# transmitter.net
KiCad netlist of a schematic drawn in EAGLE
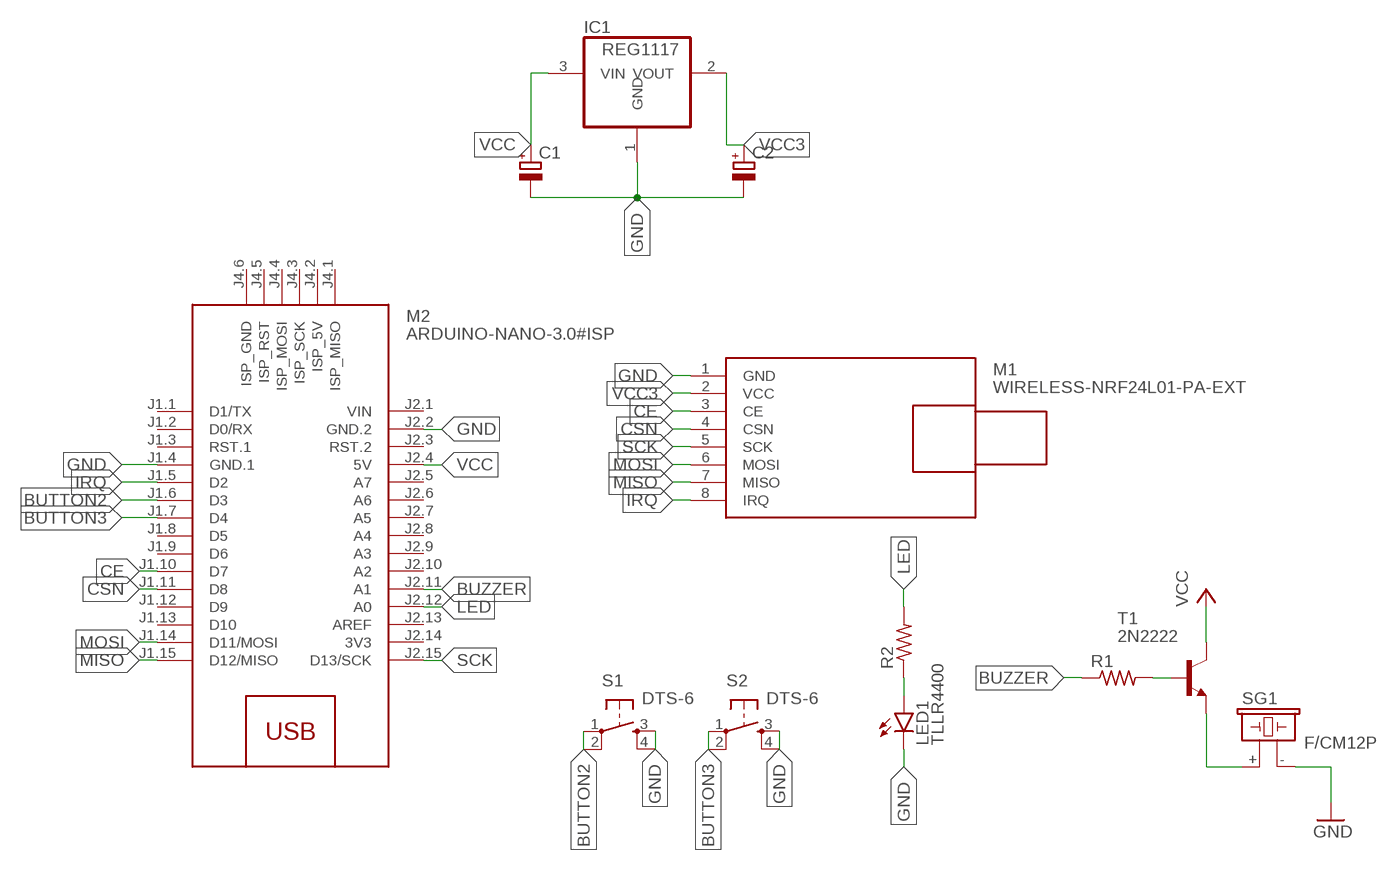
[diagram p0: schematic, sheet 1]

(export (version "E")
  (design (tool "Eeschema 10.0.6"))
  (components
    (comp (ref "C1")
      (value "CPOL-EUE2,5-6E")
      (footprint "eagle-import:E2,5-6E")
      (libsource (lib "eagle-import") (part "CPOL-EUE2,5-6E"))
    )
    (comp (ref "C2")
      (value "CPOL-EUE2,5-6E")
      (footprint "eagle-import:E2,5-6E")
      (libsource (lib "eagle-import") (part "CPOL-EUE2,5-6E"))
    )
    (comp (ref "IC1")
      (value "REG1117")
      (footprint "eagle-import:SOT223")
      (libsource (lib "eagle-import") (part "REG1117"))
    )
    (comp (ref "LED1")
      (value "TLLR4400")
      (footprint "eagle-import:LED3MM")
      (fields (field (name "MF") "VISHAY SEMICONDUCTOR"))
      (libsource (lib "eagle-import") (part "TLLR4400"))
    )
    (comp (ref "M1")
      (value "WIRELESS-NRF24L01-PA-EXT")
      (footprint "eagle-import:WIRELESS-NRF24L01-PA-EXT")
      (libsource (lib "eagle-import") (part "WIRELESS-NRF24L01-PA-EXT"))
    )
    (comp (ref "M2")
      (value "ARDUINO-NANO-3.0#ISP")
      (footprint "eagle-import:ARDUINO-NANO-3.0#ISP")
      (libsource (lib "eagle-import") (part "ARDUINO-NANO-3.0#ISP"))
    )
    (comp (ref "R1")
      (value "R-US_R0805")
      (footprint "eagle-import:R0805")
      (libsource (lib "eagle-import") (part "R-US_R0805"))
    )
    (comp (ref "R2")
      (value "R-US_R0805")
      (footprint "eagle-import:R0805")
      (libsource (lib "eagle-import") (part "R-US_R0805"))
    )
    (comp (ref "S1")
      (value "DTS-6")
      (footprint "eagle-import:DTS-6")
      (libsource (lib "eagle-import") (part "DTS-6"))
    )
    (comp (ref "S2")
      (value "DTS-6")
      (footprint "eagle-import:DTS-6")
      (libsource (lib "eagle-import") (part "DTS-6"))
    )
    (comp (ref "SG1")
      (value "F/CM12P")
      (footprint "eagle-import:F_CM12P")
      (libsource (lib "eagle-import") (part "F/CM12P"))
    )
    (comp (ref "T1")
      (value "2N2222")
      (footprint "eagle-import:TO92-EBC-OVAL")
      (libsource (lib "eagle-import") (part "2N2222"))
    )
  )
  (nets
    (net (code "1") (name "/3V3") (class "Default")
      (node (ref "M2") (pin "J2.14") (pinfunction "3V3_J2.14") (pintype "power_in"))
    )
    (net (code "2") (name "/VIN") (class "Default")
      (node (ref "M2") (pin "J2.1") (pinfunction "VIN_J2.1") (pintype "power_in"))
    )
    (net (code "3") (name "BUTTON2") (class "Default")
      (node (ref "M2") (pin "J1.6") (pinfunction "D3_J1.6") (pintype "bidirectional"))
      (node (ref "S1") (pin "1") (pinfunction "1_1") (pintype "passive"))
      (node (ref "S1") (pin "2") (pinfunction "2_2") (pintype "passive"))
    )
    (net (code "4") (name "BUTTON3") (class "Default")
      (node (ref "M2") (pin "J1.7") (pinfunction "D4_J1.7") (pintype "bidirectional"))
      (node (ref "S2") (pin "1") (pinfunction "1_1") (pintype "passive"))
      (node (ref "S2") (pin "2") (pinfunction "2_2") (pintype "passive"))
    )
    (net (code "5") (name "BUZZER") (class "Default")
      (node (ref "M2") (pin "J2.11") (pinfunction "A1_J2.11") (pintype "bidirectional"))
      (node (ref "R1") (pin "1") (pinfunction "1_1") (pintype "passive"))
    )
    (net (code "6") (name "CE") (class "Default")
      (node (ref "M1") (pin "3") (pinfunction "CE_3") (pintype "bidirectional"))
      (node (ref "M2") (pin "J1.10") (pinfunction "D7_J1.10") (pintype "bidirectional"))
    )
    (net (code "7") (name "CSN") (class "Default")
      (node (ref "M1") (pin "4") (pinfunction "CSN_4") (pintype "bidirectional"))
      (node (ref "M2") (pin "J1.11") (pinfunction "D8_J1.11") (pintype "bidirectional"))
    )
    (net (code "8") (name "GND") (class "Default")
      (node (ref "C1") (pin "-") (pinfunction "-_-") (pintype "passive"))
      (node (ref "C2") (pin "-") (pinfunction "-_-") (pintype "passive"))
      (node (ref "IC1") (pin "1") (pinfunction "GND_1") (pintype "power_in"))
      (node (ref "LED1") (pin "K") (pinfunction "C_K") (pintype "passive"))
      (node (ref "M1") (pin "1") (pinfunction "GND_1") (pintype "power_in"))
      (node (ref "M2") (pin "J1.4") (pinfunction "GND.1_J1.4") (pintype "power_in"))
      (node (ref "M2") (pin "J2.2") (pinfunction "GND.2_J2.2") (pintype "power_in"))
      (node (ref "S1") (pin "3") (pinfunction "3_3") (pintype "passive"))
      (node (ref "S1") (pin "4") (pinfunction "4_4") (pintype "passive"))
      (node (ref "S2") (pin "3") (pinfunction "3_3") (pintype "passive"))
      (node (ref "S2") (pin "4") (pinfunction "4_4") (pintype "passive"))
      (node (ref "SG1") (pin "-") (pinfunction "2_-") (pintype "passive"))
    )
    (net (code "9") (name "IRQ") (class "Default")
      (node (ref "M1") (pin "8") (pinfunction "IRQ_8") (pintype "bidirectional"))
      (node (ref "M2") (pin "J1.5") (pinfunction "D2_J1.5") (pintype "bidirectional"))
    )
    (net (code "10") (name "LED") (class "Default")
      (node (ref "M2") (pin "J2.12") (pinfunction "A0_J2.12") (pintype "bidirectional"))
      (node (ref "R2") (pin "2") (pinfunction "2_2") (pintype "passive"))
    )
    (net (code "11") (name "MISO") (class "Default")
      (node (ref "M1") (pin "7") (pinfunction "MISO_7") (pintype "bidirectional"))
      (node (ref "M2") (pin "J1.15") (pinfunction "D12/MISO_J1.15") (pintype "bidirectional"))
    )
    (net (code "12") (name "MOSI") (class "Default")
      (node (ref "M1") (pin "6") (pinfunction "MOSI_6") (pintype "bidirectional"))
      (node (ref "M2") (pin "J1.14") (pinfunction "D11/MOSI_J1.14") (pintype "bidirectional"))
    )
    (net (code "13") (name "Net-(LED1-PadA)") (class "Default")
      (node (ref "LED1") (pin "A") (pinfunction "A_A") (pintype "passive"))
      (node (ref "R2") (pin "1") (pinfunction "1_1") (pintype "passive"))
    )
    (net (code "14") (name "Net-(R1-Pad2)") (class "Default")
      (node (ref "R1") (pin "2") (pinfunction "2_2") (pintype "passive"))
      (node (ref "T1") (pin "B") (pinfunction "B_B") (pintype "passive"))
    )
    (net (code "15") (name "Net-(SG1-1)") (class "Default")
      (node (ref "SG1") (pin "+") (pinfunction "1_+") (pintype "passive"))
      (node (ref "T1") (pin "E") (pinfunction "E_E") (pintype "passive"))
    )
    (net (code "16") (name "SCK") (class "Default")
      (node (ref "M1") (pin "5") (pinfunction "SCK_5") (pintype "bidirectional"))
      (node (ref "M2") (pin "J2.15") (pinfunction "D13/SCK_J2.15") (pintype "bidirectional"))
    )
    (net (code "17") (name "VCC") (class "Default")
      (node (ref "C1") (pin "+") (pinfunction "+_+") (pintype "passive"))
      (node (ref "IC1") (pin "3") (pinfunction "VIN_3") (pintype "input"))
      (node (ref "M2") (pin "J2.4") (pinfunction "5V_J2.4") (pintype "power_in"))
      (node (ref "T1") (pin "C") (pinfunction "C_C") (pintype "passive"))
    )
    (net (code "18") (name "VCC3") (class "Default")
      (node (ref "C2") (pin "+") (pinfunction "+_+") (pintype "passive"))
      (node (ref "IC1") (pin "2") (pinfunction "VOUT_2") (pintype "output"))
      (node (ref "M1") (pin "2") (pinfunction "VCC_2") (pintype "power_in"))
    )
    (net (code "19") (name "unconnected-(M2-A2-PadJ2.10)") (class "Default")
      (node (ref "M2") (pin "J2.10") (pinfunction "A2_J2.10") (pintype "bidirectional"))
    )
    (net (code "20") (name "unconnected-(M2-A3-PadJ2.9)") (class "Default")
      (node (ref "M2") (pin "J2.9") (pinfunction "A3_J2.9") (pintype "bidirectional"))
    )
    (net (code "21") (name "unconnected-(M2-A4-PadJ2.8)") (class "Default")
      (node (ref "M2") (pin "J2.8") (pinfunction "A4_J2.8") (pintype "bidirectional"))
    )
    (net (code "22") (name "unconnected-(M2-A5-PadJ2.7)") (class "Default")
      (node (ref "M2") (pin "J2.7") (pinfunction "A5_J2.7") (pintype "bidirectional"))
    )
    (net (code "23") (name "unconnected-(M2-A6-PadJ2.6)") (class "Default")
      (node (ref "M2") (pin "J2.6") (pinfunction "A6_J2.6") (pintype "bidirectional"))
    )
    (net (code "24") (name "unconnected-(M2-A7-PadJ2.5)") (class "Default")
      (node (ref "M2") (pin "J2.5") (pinfunction "A7_J2.5") (pintype "bidirectional"))
    )
    (net (code "25") (name "unconnected-(M2-AREF-PadJ2.13)") (class "Default")
      (node (ref "M2") (pin "J2.13") (pinfunction "AREF_J2.13") (pintype "bidirectional"))
    )
    (net (code "26") (name "unconnected-(M2-D0{slash}RX-PadJ1.2)") (class "Default")
      (node (ref "M2") (pin "J1.2") (pinfunction "D0/RX_J1.2") (pintype "bidirectional"))
    )
    (net (code "27") (name "unconnected-(M2-D1{slash}TX-PadJ1.1)") (class "Default")
      (node (ref "M2") (pin "J1.1") (pinfunction "D1/TX_J1.1") (pintype "bidirectional"))
    )
    (net (code "28") (name "unconnected-(M2-D5-PadJ1.8)") (class "Default")
      (node (ref "M2") (pin "J1.8") (pinfunction "D5_J1.8") (pintype "bidirectional"))
    )
    (net (code "29") (name "unconnected-(M2-D6-PadJ1.9)") (class "Default")
      (node (ref "M2") (pin "J1.9") (pinfunction "D6_J1.9") (pintype "bidirectional"))
    )
    (net (code "30") (name "unconnected-(M2-D9-PadJ1.12)") (class "Default")
      (node (ref "M2") (pin "J1.12") (pinfunction "D9_J1.12") (pintype "bidirectional"))
    )
    (net (code "31") (name "unconnected-(M2-D10-PadJ1.13)") (class "Default")
      (node (ref "M2") (pin "J1.13") (pinfunction "D10_J1.13") (pintype "bidirectional"))
    )
    (net (code "32") (name "unconnected-(M2-ISP_5V-PadJ4.2)") (class "Default")
      (node (ref "M2") (pin "J4.2") (pinfunction "ISP_5V_J4.2") (pintype "bidirectional"))
    )
    (net (code "33") (name "unconnected-(M2-ISP_GND-PadJ4.6)") (class "Default")
      (node (ref "M2") (pin "J4.6") (pinfunction "ISP_GND_J4.6") (pintype "bidirectional"))
    )
    (net (code "34") (name "unconnected-(M2-ISP_MISO-PadJ4.1)") (class "Default")
      (node (ref "M2") (pin "J4.1") (pinfunction "ISP_MISO_J4.1") (pintype "bidirectional"))
    )
    (net (code "35") (name "unconnected-(M2-ISP_MOSI-PadJ4.4)") (class "Default")
      (node (ref "M2") (pin "J4.4") (pinfunction "ISP_MOSI_J4.4") (pintype "bidirectional"))
    )
    (net (code "36") (name "unconnected-(M2-ISP_RST-PadJ4.5)") (class "Default")
      (node (ref "M2") (pin "J4.5") (pinfunction "ISP_RST_J4.5") (pintype "bidirectional"))
    )
    (net (code "37") (name "unconnected-(M2-ISP_SCK-PadJ4.3)") (class "Default")
      (node (ref "M2") (pin "J4.3") (pinfunction "ISP_SCK_J4.3") (pintype "bidirectional"))
    )
    (net (code "38") (name "unconnected-(M2-RST.1-PadJ1.3)") (class "Default")
      (node (ref "M2") (pin "J1.3") (pinfunction "RST.1_J1.3") (pintype "bidirectional"))
    )
    (net (code "39") (name "unconnected-(M2-RST.2-PadJ2.3)") (class "Default")
      (node (ref "M2") (pin "J2.3") (pinfunction "RST.2_J2.3") (pintype "bidirectional"))
    )
  )
)
